# BT_Audio_iJoey.net
KiCad netlist of a schematic drawn in EAGLE
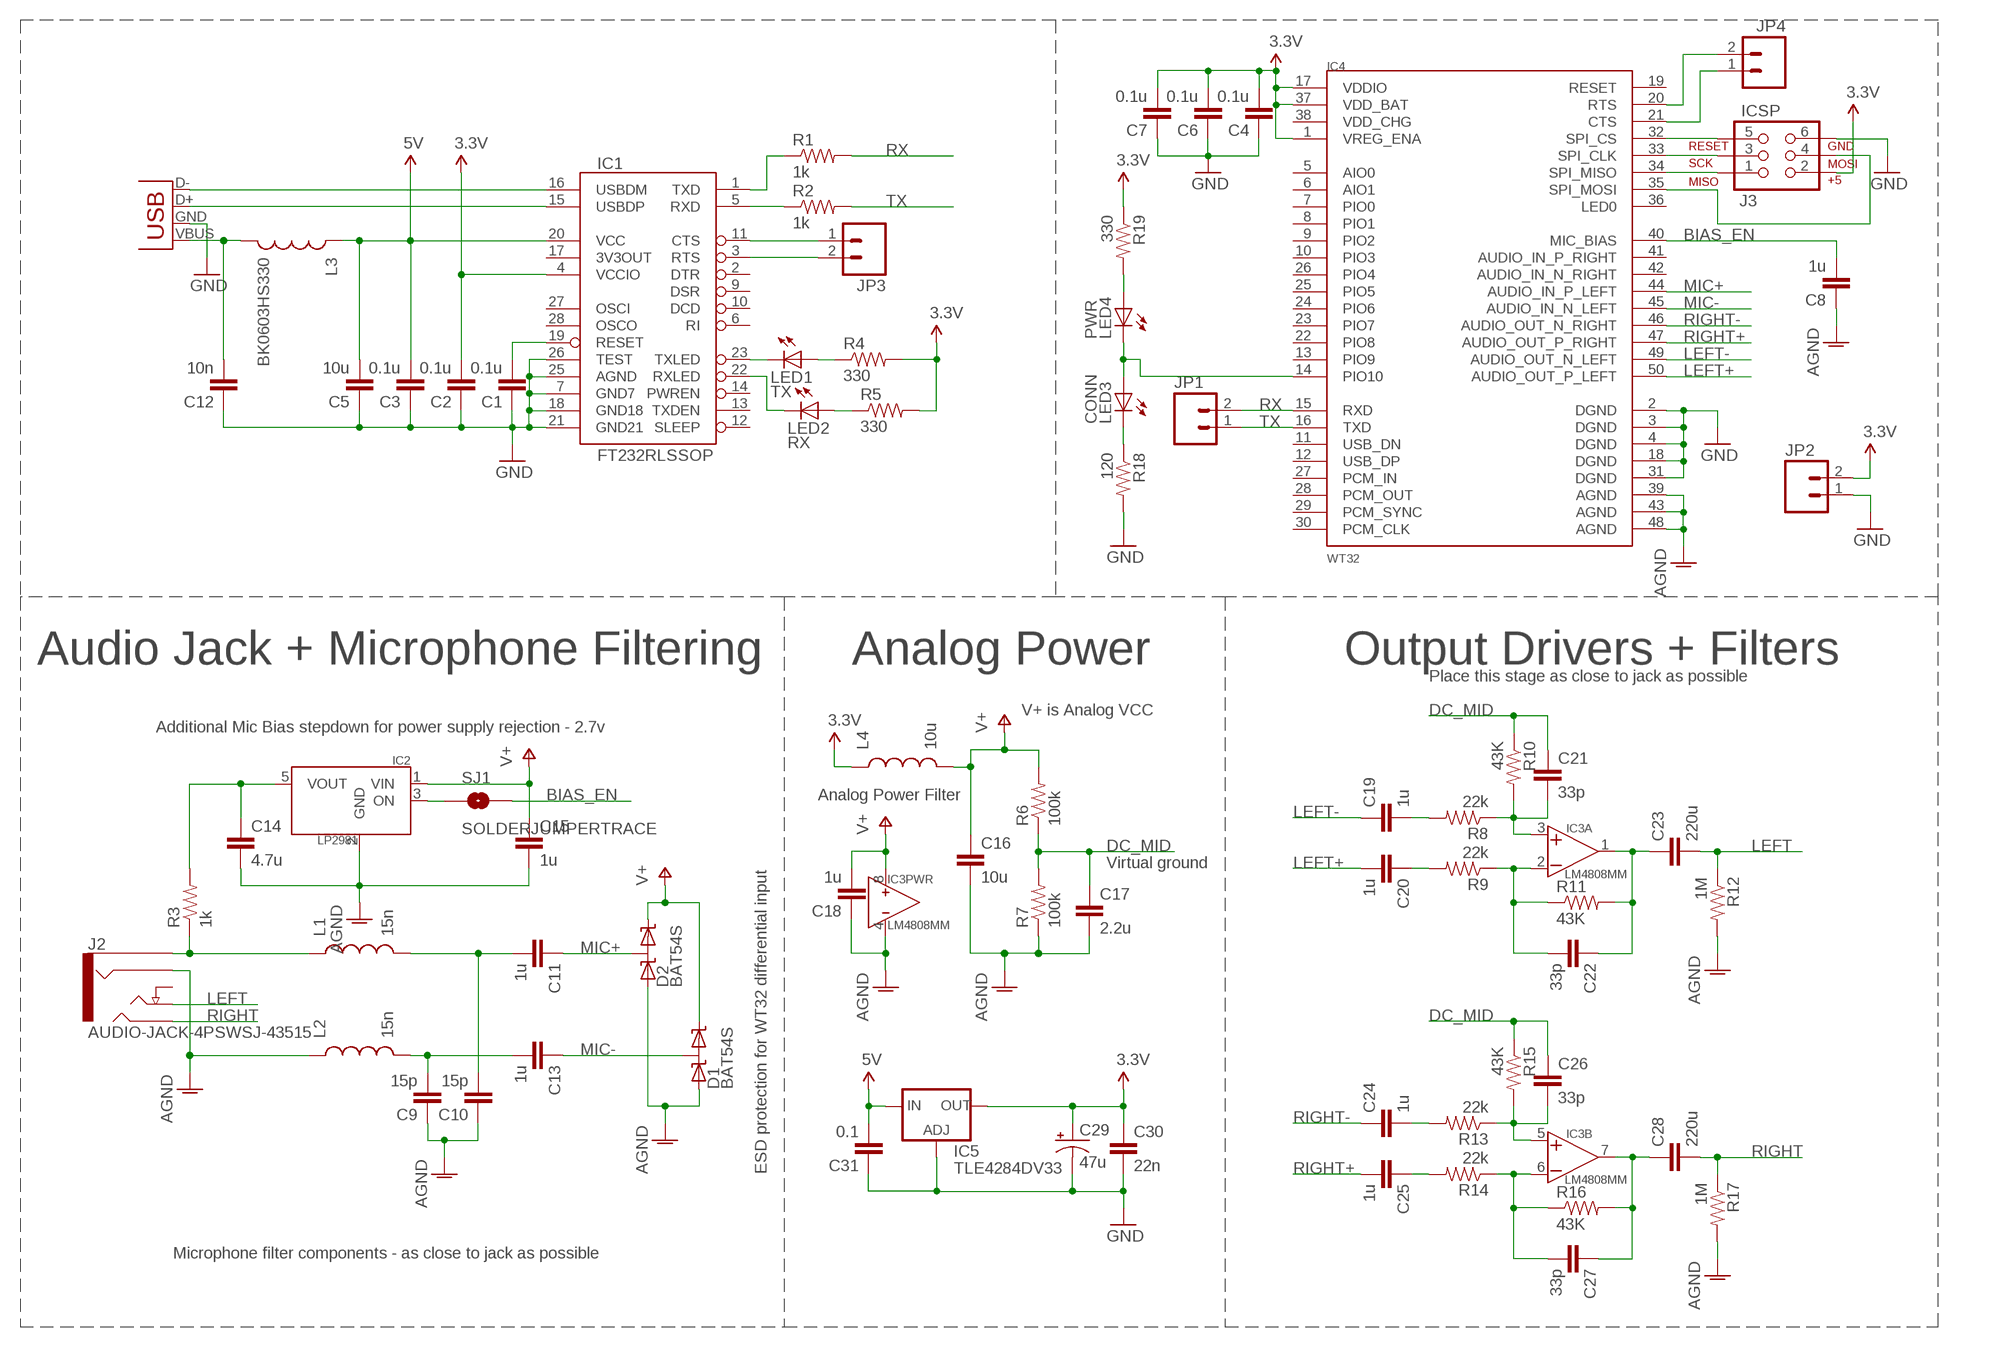
[diagram p0: schematic, sheet 1]

(export (version "E")
  (design (tool "Eeschema 10.0.6"))
  (components
    (comp (ref "C1")
      (value "0.1u")
      (footprint "eagle-import:0603-CAP")
      (libsource (lib "eagle-import") (part "CAP0603-CAP"))
    )
    (comp (ref "C2")
      (value "0.1u")
      (footprint "eagle-import:0603-CAP")
      (libsource (lib "eagle-import") (part "CAP0603-CAP"))
    )
    (comp (ref "C3")
      (value "0.1u")
      (footprint "eagle-import:0603-CAP")
      (libsource (lib "eagle-import") (part "CAP0603-CAP"))
    )
    (comp (ref "C4")
      (value "0.1u")
      (footprint "eagle-import:0603-CAP")
      (libsource (lib "eagle-import") (part "CAP0603-CAP"))
    )
    (comp (ref "C5")
      (value "10u")
      (footprint "eagle-import:0805")
      (libsource (lib "eagle-import") (part "CAP0805"))
    )
    (comp (ref "C6")
      (value "0.1u")
      (footprint "eagle-import:0603-CAP")
      (libsource (lib "eagle-import") (part "CAP0603-CAP"))
    )
    (comp (ref "C7")
      (value "0.1u")
      (footprint "eagle-import:0603-CAP")
      (libsource (lib "eagle-import") (part "CAP0603-CAP"))
    )
    (comp (ref "C8")
      (value "1u")
      (footprint "eagle-import:0603-CAP")
      (libsource (lib "eagle-import") (part "CAP0603-CAP"))
    )
    (comp (ref "C9")
      (value "15p")
      (footprint "eagle-import:0603-CAP")
      (libsource (lib "eagle-import") (part "CAP0603-CAP"))
    )
    (comp (ref "C10")
      (value "15p")
      (footprint "eagle-import:0603-CAP")
      (libsource (lib "eagle-import") (part "CAP0603-CAP"))
    )
    (comp (ref "C11")
      (value "1u")
      (footprint "eagle-import:0603-CAP")
      (libsource (lib "eagle-import") (part "CAP0603-CAP"))
    )
    (comp (ref "C12")
      (value "10n")
      (footprint "eagle-import:0603-CAP")
      (libsource (lib "eagle-import") (part "CAP0603-CAP"))
    )
    (comp (ref "C13")
      (value "1u")
      (footprint "eagle-import:0603-CAP")
      (libsource (lib "eagle-import") (part "CAP0603-CAP"))
    )
    (comp (ref "C14")
      (value "4.7u")
      (footprint "eagle-import:0603-CAP")
      (libsource (lib "eagle-import") (part "CAP0603-CAP"))
    )
    (comp (ref "C15")
      (value "1u")
      (footprint "eagle-import:0603-CAP")
      (libsource (lib "eagle-import") (part "CAP0603-CAP"))
    )
    (comp (ref "C16")
      (value "10u")
      (footprint "eagle-import:0603-CAP")
      (libsource (lib "eagle-import") (part "CAP0603-CAP"))
    )
    (comp (ref "C17")
      (value "2.2u")
      (footprint "eagle-import:0603-CAP")
      (libsource (lib "eagle-import") (part "CAP0603-CAP"))
    )
    (comp (ref "C18")
      (value "1u")
      (footprint "eagle-import:0603-CAP")
      (libsource (lib "eagle-import") (part "CAP0603-CAP"))
    )
    (comp (ref "C19")
      (value "1u")
      (footprint "eagle-import:0603-CAP")
      (libsource (lib "eagle-import") (part "CAP0603-CAP"))
    )
    (comp (ref "C20")
      (value "1u")
      (footprint "eagle-import:0603-CAP")
      (libsource (lib "eagle-import") (part "CAP0603-CAP"))
    )
    (comp (ref "C21")
      (value "33p")
      (footprint "eagle-import:0603-CAP")
      (libsource (lib "eagle-import") (part "CAP0603-CAP"))
    )
    (comp (ref "C22")
      (value "33p")
      (footprint "eagle-import:0603-CAP")
      (libsource (lib "eagle-import") (part "CAP0603-CAP"))
    )
    (comp (ref "C23")
      (value "220u")
      (footprint "eagle-import:1210")
      (libsource (lib "eagle-import") (part "CAP1210"))
    )
    (comp (ref "C24")
      (value "1u")
      (footprint "eagle-import:0603-CAP")
      (libsource (lib "eagle-import") (part "CAP0603-CAP"))
    )
    (comp (ref "C25")
      (value "1u")
      (footprint "eagle-import:0603-CAP")
      (libsource (lib "eagle-import") (part "CAP0603-CAP"))
    )
    (comp (ref "C26")
      (value "33p")
      (footprint "eagle-import:0603-CAP")
      (libsource (lib "eagle-import") (part "CAP0603-CAP"))
    )
    (comp (ref "C27")
      (value "33p")
      (footprint "eagle-import:0603-CAP")
      (libsource (lib "eagle-import") (part "CAP0603-CAP"))
    )
    (comp (ref "C28")
      (value "220u")
      (footprint "eagle-import:1210")
      (libsource (lib "eagle-import") (part "CAP1210"))
    )
    (comp (ref "C29")
      (value "47u")
      (footprint "eagle-import:PANASONIC_D")
      (libsource (lib "eagle-import") (part "CAP_POLD"))
    )
    (comp (ref "C30")
      (value "22n")
      (footprint "eagle-import:0603-CAP")
      (libsource (lib "eagle-import") (part "CAP0603-CAP"))
    )
    (comp (ref "C31")
      (value "0.1")
      (footprint "eagle-import:0603-CAP")
      (libsource (lib "eagle-import") (part "CAP0603-CAP"))
    )
    (comp (ref "D1")
      (value "BAT54S")
      (footprint "eagle-import:SOT23")
      (libsource (lib "eagle-import") (part "DIODE_DUAL_CLAMP"))
    )
    (comp (ref "D2")
      (value "BAT54S")
      (footprint "eagle-import:SOT23")
      (libsource (lib "eagle-import") (part "DIODE_DUAL_CLAMP"))
    )
    (comp (ref "IC1")
      (value "FT232RLSSOP")
      (footprint "eagle-import:SSOP28DB")
      (libsource (lib "eagle-import") (part "FT232RLSSOP"))
    )
    (comp (ref "IC2")
      (value "LP2981")
      (footprint "eagle-import:SOT23-5")
      (libsource (lib "eagle-import") (part "LP2981"))
    )
    (comp (ref "IC3")
      (value "LM4808MM")
      (footprint "eagle-import:SO8")
      (libsource (lib "eagle-import") (part "LM4808MM"))
    )
    (comp (ref "IC4")
      (value "WT32")
      (footprint "eagle-import:WT32")
      (libsource (lib "eagle-import") (part "WT32"))
    )
    (comp (ref "IC5")
      (value "TLE4284DV33")
      (footprint "eagle-import:V-REG_DPACK")
      (libsource (lib "eagle-import") (part "V_REG_317DPACK"))
    )
    (comp (ref "J1")
      (value "USB-A-H")
      (footprint "eagle-import:USB-A-H")
      (libsource (lib "eagle-import") (part "USB-A-H"))
    )
    (comp (ref "J2")
      (value "AUDIO-JACK-4PSWSJ-43515")
      (footprint "eagle-import:SJ-4351X")
      (libsource (lib "eagle-import") (part "AUDIO-JACK-4PSWSJ-43515"))
    )
    (comp (ref "J3")
      (value "ICSP")
      (footprint "eagle-import:2X3")
      (libsource (lib "eagle-import") (part "AVR_SPI_PRG_6PTH"))
    )
    (comp (ref "JP1")
      (value "M02PTH")
      (footprint "eagle-import:1X02")
      (libsource (lib "eagle-import") (part "M02PTH"))
    )
    (comp (ref "JP2")
      (value "M02PTH")
      (footprint "eagle-import:1X02")
      (libsource (lib "eagle-import") (part "M02PTH"))
    )
    (comp (ref "JP3")
      (value "M02PTH")
      (footprint "eagle-import:1X02")
      (libsource (lib "eagle-import") (part "M02PTH"))
    )
    (comp (ref "JP4")
      (value "M02PTH")
      (footprint "eagle-import:1X02")
      (libsource (lib "eagle-import") (part "M02PTH"))
    )
    (comp (ref "L1")
      (value "15n")
      (footprint "eagle-import:0603")
      (libsource (lib "eagle-import") (part "INDUCTOR0603"))
    )
    (comp (ref "L2")
      (value "15n")
      (footprint "eagle-import:0603")
      (libsource (lib "eagle-import") (part "INDUCTOR0603"))
    )
    (comp (ref "L3")
      (value "BK0603HS330")
      (footprint "eagle-import:0603")
      (libsource (lib "eagle-import") (part "INDUCTOR0603"))
    )
    (comp (ref "L4")
      (value "10u")
      (footprint "eagle-import:0603")
      (libsource (lib "eagle-import") (part "INDUCTOR0603"))
    )
    (comp (ref "LED1")
      (value "TX")
      (footprint "eagle-import:LED-0603")
      (libsource (lib "eagle-import") (part "LED0603"))
    )
    (comp (ref "LED2")
      (value "RX")
      (footprint "eagle-import:LED-0603")
      (libsource (lib "eagle-import") (part "LED0603"))
    )
    (comp (ref "LED3")
      (value "CONN")
      (footprint "eagle-import:LED-0603")
      (libsource (lib "eagle-import") (part "LED0603"))
    )
    (comp (ref "LED4")
      (value "PWR")
      (footprint "eagle-import:LED-0603")
      (libsource (lib "eagle-import") (part "LED0603"))
    )
    (comp (ref "R1")
      (value "1k")
      (footprint "eagle-import:0603-RES")
      (libsource (lib "eagle-import") (part "RESISTOR0603-RES"))
    )
    (comp (ref "R2")
      (value "1k")
      (footprint "eagle-import:0603-RES")
      (libsource (lib "eagle-import") (part "RESISTOR0603-RES"))
    )
    (comp (ref "R3")
      (value "1k")
      (footprint "eagle-import:0603-RES")
      (libsource (lib "eagle-import") (part "RESISTOR0603-RES"))
    )
    (comp (ref "R4")
      (value "330")
      (footprint "eagle-import:0603-RES")
      (libsource (lib "eagle-import") (part "RESISTOR0603-RES"))
    )
    (comp (ref "R5")
      (value "330")
      (footprint "eagle-import:0603-RES")
      (libsource (lib "eagle-import") (part "RESISTOR0603-RES"))
    )
    (comp (ref "R6")
      (value "100k")
      (footprint "eagle-import:0603-RES")
      (libsource (lib "eagle-import") (part "RESISTOR0603-RES"))
    )
    (comp (ref "R7")
      (value "100k")
      (footprint "eagle-import:0603-RES")
      (libsource (lib "eagle-import") (part "RESISTOR0603-RES"))
    )
    (comp (ref "R8")
      (value "22k")
      (footprint "eagle-import:0603-RES")
      (libsource (lib "eagle-import") (part "RESISTOR0603-RES"))
    )
    (comp (ref "R9")
      (value "22k")
      (footprint "eagle-import:0603-RES")
      (libsource (lib "eagle-import") (part "RESISTOR0603-RES"))
    )
    (comp (ref "R10")
      (value "43K")
      (footprint "eagle-import:0603-RES")
      (libsource (lib "eagle-import") (part "RESISTOR0603-RES"))
    )
    (comp (ref "R11")
      (value "43K")
      (footprint "eagle-import:0603-RES")
      (libsource (lib "eagle-import") (part "RESISTOR0603-RES"))
    )
    (comp (ref "R12")
      (value "1M")
      (footprint "eagle-import:0603-RES")
      (libsource (lib "eagle-import") (part "RESISTOR0603-RES"))
    )
    (comp (ref "R13")
      (value "22k")
      (footprint "eagle-import:0603-RES")
      (libsource (lib "eagle-import") (part "RESISTOR0603-RES"))
    )
    (comp (ref "R14")
      (value "22k")
      (footprint "eagle-import:0603-RES")
      (libsource (lib "eagle-import") (part "RESISTOR0603-RES"))
    )
    (comp (ref "R15")
      (value "43K")
      (footprint "eagle-import:0603-RES")
      (libsource (lib "eagle-import") (part "RESISTOR0603-RES"))
    )
    (comp (ref "R16")
      (value "43K")
      (footprint "eagle-import:0603-RES")
      (libsource (lib "eagle-import") (part "RESISTOR0603-RES"))
    )
    (comp (ref "R17")
      (value "1M")
      (footprint "eagle-import:0603-RES")
      (libsource (lib "eagle-import") (part "RESISTOR0603-RES"))
    )
    (comp (ref "R18")
      (value "120")
      (footprint "eagle-import:0603-RES")
      (libsource (lib "eagle-import") (part "RESISTOR0603-RES"))
    )
    (comp (ref "R19")
      (value "330")
      (footprint "eagle-import:0603-RES")
      (libsource (lib "eagle-import") (part "RESISTOR0603-RES"))
    )
    (comp (ref "SJ1")
      (value "SOLDERJUMPERTRACE")
      (footprint "eagle-import:SJ_2S-TRACE")
      (libsource (lib "eagle-import") (part "SOLDERJUMPERTRACE"))
    )
  )
  (nets
    (net (code "1") (name "/BIAS_EN") (class "Default")
      (node (ref "C8") (pin "2") (pinfunction "2_2") (pintype "passive"))
      (node (ref "IC4") (pin "40") (pinfunction "MIC_BIAS_40") (pintype "bidirectional"))
      (node (ref "SJ1") (pin "2") (pinfunction "2_2") (pintype "passive"))
    )
    (net (code "2") (name "/DC_MID") (class "Default")
      (node (ref "C17") (pin "1") (pinfunction "1_1") (pintype "passive"))
      (node (ref "C21") (pin "1") (pinfunction "1_1") (pintype "passive"))
      (node (ref "C26") (pin "1") (pinfunction "1_1") (pintype "passive"))
      (node (ref "R10") (pin "1") (pinfunction "1_1") (pintype "passive"))
      (node (ref "R15") (pin "1") (pinfunction "1_1") (pintype "passive"))
      (node (ref "R6") (pin "1") (pinfunction "1_1") (pintype "passive"))
      (node (ref "R7") (pin "2") (pinfunction "2_2") (pintype "passive"))
    )
    (net (code "3") (name "/LEFT") (class "Default")
      (node (ref "C23") (pin "2") (pinfunction "2_2") (pintype "passive"))
      (node (ref "J2") (pin "2") (pinfunction "TIP_2") (pintype "bidirectional"))
      (node (ref "R12") (pin "1") (pinfunction "1_1") (pintype "passive"))
    )
    (net (code "4") (name "/LEFT+") (class "Default")
      (node (ref "C20") (pin "2") (pinfunction "2_2") (pintype "passive"))
      (node (ref "IC4") (pin "50") (pinfunction "AUDIO_OUT_P_LEFT_50") (pintype "bidirectional"))
    )
    (net (code "5") (name "/LEFT-") (class "Default")
      (node (ref "C19") (pin "1") (pinfunction "1_1") (pintype "passive"))
      (node (ref "IC4") (pin "49") (pinfunction "AUDIO_OUT_N_LEFT_49") (pintype "bidirectional"))
    )
    (net (code "6") (name "/MIC+") (class "Default")
      (node (ref "C11") (pin "1") (pinfunction "1_1") (pintype "passive"))
      (node (ref "D2") (pin "3") (pinfunction "COM_3") (pintype "passive"))
      (node (ref "IC4") (pin "44") (pinfunction "AUDIO_IN_P_LEFT_44") (pintype "bidirectional"))
    )
    (net (code "7") (name "/MIC-") (class "Default")
      (node (ref "C13") (pin "1") (pinfunction "1_1") (pintype "passive"))
      (node (ref "D1") (pin "3") (pinfunction "COM_3") (pintype "passive"))
      (node (ref "IC4") (pin "45") (pinfunction "AUDIO_IN_N_LEFT_45") (pintype "bidirectional"))
    )
    (net (code "8") (name "/RIGHT") (class "Default")
      (node (ref "C28") (pin "2") (pinfunction "2_2") (pintype "passive"))
      (node (ref "J2") (pin "3") (pinfunction "RING1_3") (pintype "bidirectional"))
      (node (ref "R17") (pin "1") (pinfunction "1_1") (pintype "passive"))
    )
    (net (code "9") (name "/RIGHT+") (class "Default")
      (node (ref "C25") (pin "2") (pinfunction "2_2") (pintype "passive"))
      (node (ref "IC4") (pin "47") (pinfunction "AUDIO_OUT_P_RIGHT_47") (pintype "bidirectional"))
    )
    (net (code "10") (name "/RIGHT-") (class "Default")
      (node (ref "C24") (pin "1") (pinfunction "1_1") (pintype "passive"))
      (node (ref "IC4") (pin "46") (pinfunction "AUDIO_OUT_N_RIGHT_46") (pintype "bidirectional"))
    )
    (net (code "11") (name "/RX") (class "Default")
      (node (ref "IC4") (pin "15") (pinfunction "RXD_15") (pintype "bidirectional"))
      (node (ref "JP1") (pin "2") (pinfunction "2_2") (pintype "passive"))
      (node (ref "R1") (pin "2") (pinfunction "2_2") (pintype "passive"))
    )
    (net (code "12") (name "/TX") (class "Default")
      (node (ref "IC4") (pin "16") (pinfunction "TXD_16") (pintype "bidirectional"))
      (node (ref "JP1") (pin "1") (pinfunction "1_1") (pintype "passive"))
      (node (ref "R2") (pin "2") (pinfunction "2_2") (pintype "passive"))
    )
    (net (code "13") (name "3.3V") (class "Default")
      (node (ref "C2") (pin "2") (pinfunction "2_2") (pintype "passive"))
      (node (ref "C29") (pin "+") (pinfunction "+_+") (pintype "passive"))
      (node (ref "C30") (pin "1") (pinfunction "1_1") (pintype "passive"))
      (node (ref "C4") (pin "2") (pinfunction "2_2") (pintype "passive"))
      (node (ref "C6") (pin "2") (pinfunction "2_2") (pintype "passive"))
      (node (ref "C7") (pin "2") (pinfunction "2_2") (pintype "passive"))
      (node (ref "IC1") (pin "4") (pinfunction "VCCIO_4") (pintype "power_in"))
      (node (ref "IC4") (pin "1") (pinfunction "VREG_ENA_1") (pintype "bidirectional"))
      (node (ref "IC4") (pin "17") (pinfunction "VDDIO_17") (pintype "bidirectional"))
      (node (ref "IC4") (pin "37") (pinfunction "VDD_BAT_37") (pintype "bidirectional"))
      (node (ref "IC5") (pin "4") (pinfunction "OUT_4") (pintype "output"))
      (node (ref "J3") (pin "2") (pinfunction "2_2") (pintype "passive"))
      (node (ref "JP2") (pin "2") (pinfunction "2_2") (pintype "passive"))
      (node (ref "L4") (pin "1") (pinfunction "1_1") (pintype "passive"))
      (node (ref "R19") (pin "1") (pinfunction "1_1") (pintype "passive"))
      (node (ref "R4") (pin "2") (pinfunction "2_2") (pintype "passive"))
      (node (ref "R5") (pin "2") (pinfunction "2_2") (pintype "passive"))
    )
    (net (code "14") (name "5V") (class "Default")
      (node (ref "C3") (pin "2") (pinfunction "2_2") (pintype "passive"))
      (node (ref "C31") (pin "2") (pinfunction "2_2") (pintype "passive"))
      (node (ref "C5") (pin "2") (pinfunction "2_2") (pintype "passive"))
      (node (ref "IC1") (pin "20") (pinfunction "VCC_20") (pintype "power_in"))
      (node (ref "IC5") (pin "3") (pinfunction "IN_3") (pintype "input"))
      (node (ref "L3") (pin "1") (pinfunction "1_1") (pintype "passive"))
    )
    (net (code "15") (name "AGND") (class "Default")
      (node (ref "C10") (pin "1") (pinfunction "1_1") (pintype "passive"))
      (node (ref "C14") (pin "2") (pinfunction "2_2") (pintype "passive"))
      (node (ref "C15") (pin "2") (pinfunction "2_2") (pintype "passive"))
      (node (ref "C16") (pin "2") (pinfunction "2_2") (pintype "passive"))
      (node (ref "C17") (pin "2") (pinfunction "2_2") (pintype "passive"))
      (node (ref "C18") (pin "1") (pinfunction "1_1") (pintype "passive"))
      (node (ref "C8") (pin "1") (pinfunction "1_1") (pintype "passive"))
      (node (ref "C9") (pin "1") (pinfunction "1_1") (pintype "passive"))
      (node (ref "D1") (pin "1") (pinfunction "AN_1") (pintype "passive"))
      (node (ref "D2") (pin "1") (pinfunction "AN_1") (pintype "passive"))
      (node (ref "IC2") (pin "2") (pinfunction "GND_2") (pintype "bidirectional"))
      (node (ref "IC3") (pin "4") (pinfunction "-V_4") (pintype "bidirectional"))
      (node (ref "IC4") (pin "39") (pinfunction "AGND_39") (pintype "bidirectional"))
      (node (ref "IC4") (pin "43") (pinfunction "AGND_43") (pintype "bidirectional"))
      (node (ref "IC4") (pin "48") (pinfunction "AGND_48") (pintype "bidirectional"))
      (node (ref "J2") (pin "4") (pinfunction "RING2_4") (pintype "bidirectional"))
      (node (ref "L2") (pin "1") (pinfunction "1_1") (pintype "passive"))
      (node (ref "R12") (pin "2") (pinfunction "2_2") (pintype "passive"))
      (node (ref "R17") (pin "2") (pinfunction "2_2") (pintype "passive"))
      (node (ref "R7") (pin "1") (pinfunction "1_1") (pintype "passive"))
    )
    (net (code "16") (name "GND") (class "Default")
      (node (ref "C1") (pin "1") (pinfunction "1_1") (pintype "passive"))
      (node (ref "C12") (pin "1") (pinfunction "1_1") (pintype "passive"))
      (node (ref "C2") (pin "1") (pinfunction "1_1") (pintype "passive"))
      (node (ref "C29") (pin "-") (pinfunction "-_-") (pintype "passive"))
      (node (ref "C3") (pin "1") (pinfunction "1_1") (pintype "passive"))
      (node (ref "C30") (pin "2") (pinfunction "2_2") (pintype "passive"))
      (node (ref "C31") (pin "1") (pinfunction "1_1") (pintype "passive"))
      (node (ref "C4") (pin "1") (pinfunction "1_1") (pintype "passive"))
      (node (ref "C5") (pin "1") (pinfunction "1_1") (pintype "passive"))
      (node (ref "C6") (pin "1") (pinfunction "1_1") (pintype "passive"))
      (node (ref "C7") (pin "1") (pinfunction "1_1") (pintype "passive"))
      (node (ref "IC1") (pin "18") (pinfunction "GND18_18") (pintype "power_in"))
      (node (ref "IC1") (pin "21") (pinfunction "GND21_21") (pintype "power_in"))
      (node (ref "IC1") (pin "25") (pinfunction "AGND_25") (pintype "power_in"))
      (node (ref "IC1") (pin "26") (pinfunction "TEST_26") (pintype "input"))
      (node (ref "IC1") (pin "7") (pinfunction "GND7_7") (pintype "power_in"))
      (node (ref "IC4") (pin "18") (pinfunction "DGND_18") (pintype "bidirectional"))
      (node (ref "IC4") (pin "2") (pinfunction "DGND_2") (pintype "bidirectional"))
      (node (ref "IC4") (pin "3") (pinfunction "DGND_3") (pintype "bidirectional"))
      (node (ref "IC4") (pin "31") (pinfunction "DGND_31") (pintype "bidirectional"))
      (node (ref "IC4") (pin "4") (pinfunction "DGND_4") (pintype "bidirectional"))
      (node (ref "IC5") (pin "1") (pinfunction "ADJ_1") (pintype "input"))
      (node (ref "J1") (pin "GND") (pinfunction "VBUS_GND") (pintype "bidirectional"))
      (node (ref "J3") (pin "6") (pinfunction "6_6") (pintype "passive"))
      (node (ref "JP2") (pin "1") (pinfunction "1_1") (pintype "passive"))
      (node (ref "R18") (pin "2") (pinfunction "2_2") (pintype "passive"))
    )
    (net (code "17") (name "Net-(C10-Pad2)") (class "Default")
      (node (ref "C10") (pin "2") (pinfunction "2_2") (pintype "passive"))
      (node (ref "C11") (pin "2") (pinfunction "2_2") (pintype "passive"))
      (node (ref "L1") (pin "2") (pinfunction "2_2") (pintype "passive"))
    )
    (net (code "18") (name "Net-(C13-Pad2)") (class "Default")
      (node (ref "C13") (pin "2") (pinfunction "2_2") (pintype "passive"))
      (node (ref "C9") (pin "2") (pinfunction "2_2") (pintype "passive"))
      (node (ref "L2") (pin "2") (pinfunction "2_2") (pintype "passive"))
    )
    (net (code "19") (name "Net-(C19-Pad2)") (class "Default")
      (node (ref "C19") (pin "2") (pinfunction "2_2") (pintype "passive"))
      (node (ref "R8") (pin "2") (pinfunction "2_2") (pintype "passive"))
    )
    (net (code "20") (name "Net-(C20-Pad1)") (class "Default")
      (node (ref "C20") (pin "1") (pinfunction "1_1") (pintype "passive"))
      (node (ref "R9") (pin "2") (pinfunction "2_2") (pintype "passive"))
    )
    (net (code "21") (name "Net-(C24-Pad2)") (class "Default")
      (node (ref "C24") (pin "2") (pinfunction "2_2") (pintype "passive"))
      (node (ref "R13") (pin "2") (pinfunction "2_2") (pintype "passive"))
    )
    (net (code "22") (name "Net-(C25-Pad1)") (class "Default")
      (node (ref "C25") (pin "1") (pinfunction "1_1") (pintype "passive"))
      (node (ref "R14") (pin "2") (pinfunction "2_2") (pintype "passive"))
    )
    (net (code "23") (name "Net-(IC1-CTS)") (class "Default")
      (node (ref "IC1") (pin "11") (pinfunction "CTS_11") (pintype "input"))
      (node (ref "JP3") (pin "1") (pinfunction "1_1") (pintype "passive"))
    )
    (net (code "24") (name "Net-(IC1-RESET)") (class "Default")
      (node (ref "C1") (pin "2") (pinfunction "2_2") (pintype "passive"))
      (node (ref "IC1") (pin "19") (pinfunction "RESET_19") (pintype "input"))
    )
    (net (code "25") (name "Net-(IC1-RTS)") (class "Default")
      (node (ref "IC1") (pin "3") (pinfunction "RTS_3") (pintype "output"))
      (node (ref "JP3") (pin "2") (pinfunction "2_2") (pintype "passive"))
    )
    (net (code "26") (name "Net-(IC1-RXD)") (class "Default")
      (node (ref "IC1") (pin "5") (pinfunction "RXD_5") (pintype "input"))
      (node (ref "R2") (pin "1") (pinfunction "1_1") (pintype "passive"))
    )
    (net (code "27") (name "Net-(IC1-RXLED)") (class "Default")
      (node (ref "IC1") (pin "22") (pinfunction "RXLED_22") (pintype "input"))
      (node (ref "LED2") (pin "C") (pinfunction "C_C") (pintype "passive"))
    )
    (net (code "28") (name "Net-(IC1-TXD)") (class "Default")
      (node (ref "IC1") (pin "1") (pinfunction "TXD_1") (pintype "output"))
      (node (ref "R1") (pin "1") (pinfunction "1_1") (pintype "passive"))
    )
    (net (code "29") (name "Net-(IC1-TXLED)") (class "Default")
      (node (ref "IC1") (pin "23") (pinfunction "TXLED_23") (pintype "input"))
      (node (ref "LED1") (pin "C") (pinfunction "C_C") (pintype "passive"))
    )
    (net (code "30") (name "Net-(IC1-USBDM)") (class "Default")
      (node (ref "IC1") (pin "16") (pinfunction "USBDM_16") (pintype "bidirectional"))
      (node (ref "J1") (pin "D-") (pinfunction "D+_D-") (pintype "bidirectional"))
    )
    (net (code "31") (name "Net-(IC1-USBDP)") (class "Default")
      (node (ref "IC1") (pin "15") (pinfunction "USBDP_15") (pintype "bidirectional"))
      (node (ref "J1") (pin "D+") (pinfunction "D-_D+") (pintype "bidirectional"))
    )
    (net (code "32") (name "Net-(IC2-ON)") (class "Default")
      (node (ref "IC2") (pin "3") (pinfunction "ON_3") (pintype "bidirectional"))
      (node (ref "SJ1") (pin "1") (pinfunction "1_1") (pintype "passive"))
    )
    (net (code "33") (name "Net-(IC2-VOUT)") (class "Default")
      (node (ref "C14") (pin "1") (pinfunction "1_1") (pintype "passive"))
      (node (ref "IC2") (pin "5") (pinfunction "VOUT_5") (pintype "bidirectional"))
      (node (ref "R3") (pin "2") (pinfunction "2_2") (pintype "passive"))
    )
    (net (code "34") (name "Net-(IC3A-+)") (class "Default")
      (node (ref "C21") (pin "2") (pinfunction "2_2") (pintype "passive"))
      (node (ref "IC3") (pin "3") (pinfunction "+_3") (pintype "bidirectional"))
      (node (ref "R10") (pin "2") (pinfunction "2_2") (pintype "passive"))
      (node (ref "R8") (pin "1") (pinfunction "1_1") (pintype "passive"))
    )
    (net (code "35") (name "Net-(IC3A--)") (class "Default")
      (node (ref "C22") (pin "2") (pinfunction "2_2") (pintype "passive"))
      (node (ref "IC3") (pin "2") (pinfunction "-_2") (pintype "bidirectional"))
      (node (ref "R11") (pin "1") (pinfunction "1_1") (pintype "passive"))
      (node (ref "R9") (pin "1") (pinfunction "1_1") (pintype "passive"))
    )
    (net (code "36") (name "Net-(IC3A-O)") (class "Default")
      (node (ref "C22") (pin "1") (pinfunction "1_1") (pintype "passive"))
      (node (ref "C23") (pin "1") (pinfunction "1_1") (pintype "passive"))
      (node (ref "IC3") (pin "1") (pinfunction "O_1") (pintype "bidirectional"))
      (node (ref "R11") (pin "2") (pinfunction "2_2") (pintype "passive"))
    )
    (net (code "37") (name "Net-(IC3B-+)") (class "Default")
      (node (ref "C26") (pin "2") (pinfunction "2_2") (pintype "passive"))
      (node (ref "IC3") (pin "5") (pinfunction "+_5") (pintype "bidirectional"))
      (node (ref "R13") (pin "1") (pinfunction "1_1") (pintype "passive"))
      (node (ref "R15") (pin "2") (pinfunction "2_2") (pintype "passive"))
    )
    (net (code "38") (name "Net-(IC3B--)") (class "Default")
      (node (ref "C27") (pin "2") (pinfunction "2_2") (pintype "passive"))
      (node (ref "IC3") (pin "6") (pinfunction "-_6") (pintype "bidirectional"))
      (node (ref "R14") (pin "1") (pinfunction "1_1") (pintype "passive"))
      (node (ref "R16") (pin "1") (pinfunction "1_1") (pintype "passive"))
    )
    (net (code "39") (name "Net-(IC3B-O)") (class "Default")
      (node (ref "C27") (pin "1") (pinfunction "1_1") (pintype "passive"))
      (node (ref "C28") (pin "1") (pinfunction "1_1") (pintype "passive"))
      (node (ref "IC3") (pin "7") (pinfunction "O_7") (pintype "bidirectional"))
      (node (ref "R16") (pin "2") (pinfunction "2_2") (pintype "passive"))
    )
    (net (code "40") (name "Net-(IC4-CTS)") (class "Default")
      (node (ref "IC4") (pin "21") (pinfunction "CTS_21") (pintype "bidirectional"))
      (node (ref "JP4") (pin "1") (pinfunction "1_1") (pintype "passive"))
    )
    (net (code "41") (name "Net-(IC4-PIO10)") (class "Default")
      (node (ref "IC4") (pin "14") (pinfunction "PIO10_14") (pintype "bidirectional"))
      (node (ref "LED3") (pin "A") (pinfunction "A_A") (pintype "passive"))
      (node (ref "LED4") (pin "C") (pinfunction "C_C") (pintype "passive"))
    )
    (net (code "42") (name "Net-(IC4-RTS)") (class "Default")
      (node (ref "IC4") (pin "20") (pinfunction "RTS_20") (pintype "bidirectional"))
      (node (ref "JP4") (pin "2") (pinfunction "2_2") (pintype "passive"))
    )
    (net (code "43") (name "Net-(IC4-SPI_CLK)") (class "Default")
      (node (ref "IC4") (pin "33") (pinfunction "SPI_CLK_33") (pintype "bidirectional"))
      (node (ref "J3") (pin "3") (pinfunction "3_3") (pintype "passive"))
    )
    (net (code "44") (name "Net-(IC4-SPI_CS)") (class "Default")
      (node (ref "IC4") (pin "32") (pinfunction "SPI_CS_32") (pintype "bidirectional"))
      (node (ref "J3") (pin "5") (pinfunction "5_5") (pintype "passive"))
    )
    (net (code "45") (name "Net-(IC4-SPI_MISO)") (class "Default")
      (node (ref "IC4") (pin "34") (pinfunction "SPI_MISO_34") (pintype "bidirectional"))
      (node (ref "J3") (pin "1") (pinfunction "1_1") (pintype "passive"))
    )
    (net (code "46") (name "Net-(IC4-SPI_MOSI)") (class "Default")
      (node (ref "IC4") (pin "35") (pinfunction "SPI_MOSI_35") (pintype "bidirectional"))
      (node (ref "J3") (pin "4") (pinfunction "4_4") (pintype "passive"))
    )
    (net (code "47") (name "Net-(J1-GND)") (class "Default")
      (node (ref "C12") (pin "2") (pinfunction "2_2") (pintype "passive"))
      (node (ref "J1") (pin "VBUS") (pinfunction "GND_VBUS") (pintype "bidirectional"))
      (node (ref "L3") (pin "2") (pinfunction "2_2") (pintype "passive"))
    )
    (net (code "48") (name "Net-(J2-SLEEVE)") (class "Default")
      (node (ref "J2") (pin "1") (pinfunction "SLEEVE_1") (pintype "bidirectional"))
      (node (ref "L1") (pin "1") (pinfunction "1_1") (pintype "passive"))
      (node (ref "R3") (pin "1") (pinfunction "1_1") (pintype "passive"))
    )
    (net (code "49") (name "Net-(LED1-PadA)") (class "Default")
      (node (ref "LED1") (pin "A") (pinfunction "A_A") (pintype "passive"))
      (node (ref "R4") (pin "1") (pinfunction "1_1") (pintype "passive"))
    )
    (net (code "50") (name "Net-(LED2-PadA)") (class "Default")
      (node (ref "LED2") (pin "A") (pinfunction "A_A") (pintype "passive"))
      (node (ref "R5") (pin "1") (pinfunction "1_1") (pintype "passive"))
    )
    (net (code "51") (name "Net-(LED3-PadC)") (class "Default")
      (node (ref "LED3") (pin "C") (pinfunction "C_C") (pintype "passive"))
      (node (ref "R18") (pin "1") (pinfunction "1_1") (pintype "passive"))
    )
    (net (code "52") (name "Net-(LED4-PadA)") (class "Default")
      (node (ref "LED4") (pin "A") (pinfunction "A_A") (pintype "passive"))
      (node (ref "R19") (pin "2") (pinfunction "2_2") (pintype "passive"))
    )
    (net (code "53") (name "V+") (class "Default")
      (node (ref "C15") (pin "1") (pinfunction "1_1") (pintype "passive"))
      (node (ref "C16") (pin "1") (pinfunction "1_1") (pintype "passive"))
      (node (ref "C18") (pin "2") (pinfunction "2_2") (pintype "passive"))
      (node (ref "D1") (pin "2") (pinfunction "CAT_2") (pintype "passive"))
      (node (ref "D2") (pin "2") (pinfunction "CAT_2") (pintype "passive"))
      (node (ref "IC2") (pin "1") (pinfunction "VIN_1") (pintype "bidirectional"))
      (node (ref "IC3") (pin "8") (pinfunction "+V_8") (pintype "bidirectional"))
      (node (ref "L4") (pin "2") (pinfunction "2_2") (pintype "passive"))
      (node (ref "R6") (pin "2") (pinfunction "2_2") (pintype "passive"))
    )
    (net (code "54") (name "unconnected-(IC1-3V3OUT-Pad17)") (class "Default")
      (node (ref "IC1") (pin "17") (pinfunction "3V3OUT_17") (pintype "output"))
    )
    (net (code "55") (name "unconnected-(IC1-DCD-Pad10)") (class "Default")
      (node (ref "IC1") (pin "10") (pinfunction "DCD_10") (pintype "input"))
    )
    (net (code "56") (name "unconnected-(IC1-DSR-Pad9)") (class "Default")
      (node (ref "IC1") (pin "9") (pinfunction "DSR_9") (pintype "input"))
    )
    (net (code "57") (name "unconnected-(IC1-DTR-Pad2)") (class "Default")
      (node (ref "IC1") (pin "2") (pinfunction "DTR_2") (pintype "output"))
    )
    (net (code "58") (name "unconnected-(IC1-OSCI-Pad27)") (class "Default")
      (node (ref "IC1") (pin "27") (pinfunction "OSCI_27") (pintype "input"))
    )
    (net (code "59") (name "unconnected-(IC1-OSCO-Pad28)") (class "Default")
      (node (ref "IC1") (pin "28") (pinfunction "OSCO_28") (pintype "output"))
    )
    (net (code "60") (name "unconnected-(IC1-PWREN-Pad14)") (class "Default")
      (node (ref "IC1") (pin "14") (pinfunction "PWREN_14") (pintype "input"))
    )
    (net (code "61") (name "unconnected-(IC1-RI-Pad6)") (class "Default")
      (node (ref "IC1") (pin "6") (pinfunction "RI_6") (pintype "input"))
    )
    (net (code "62") (name "unconnected-(IC1-SLEEP-Pad12)") (class "Default")
      (node (ref "IC1") (pin "12") (pinfunction "SLEEP_12") (pintype "input"))
    )
    (net (code "63") (name "unconnected-(IC1-TXDEN-Pad13)") (class "Default")
      (node (ref "IC1") (pin "13") (pinfunction "TXDEN_13") (pintype "input"))
    )
    (net (code "64") (name "unconnected-(IC4-AIO0-Pad5)") (class "Default")
      (node (ref "IC4") (pin "5") (pinfunction "AIO0_5") (pintype "bidirectional"))
    )
    (net (code "65") (name "unconnected-(IC4-AIO1-Pad6)") (class "Default")
      (node (ref "IC4") (pin "6") (pinfunction "AIO1_6") (pintype "bidirectional"))
    )
    (net (code "66") (name "unconnected-(IC4-AUDIO_IN_N_RIGHT-Pad42)") (class "Default")
      (node (ref "IC4") (pin "42") (pinfunction "AUDIO_IN_N_RIGHT_42") (pintype "bidirectional"))
    )
    (net (code "67") (name "unconnected-(IC4-AUDIO_IN_P_RIGHT-Pad41)") (class "Default")
      (node (ref "IC4") (pin "41") (pinfunction "AUDIO_IN_P_RIGHT_41") (pintype "bidirectional"))
    )
    (net (code "68") (name "unconnected-(IC4-LED0-Pad36)") (class "Default")
      (node (ref "IC4") (pin "36") (pinfunction "LED0_36") (pintype "bidirectional"))
    )
    (net (code "69") (name "unconnected-(IC4-PCM_CLK-Pad30)") (class "Default")
      (node (ref "IC4") (pin "30") (pinfunction "PCM_CLK_30") (pintype "bidirectional"))
    )
    (net (code "70") (name "unconnected-(IC4-PCM_IN-Pad27)") (class "Default")
      (node (ref "IC4") (pin "27") (pinfunction "PCM_IN_27") (pintype "bidirectional"))
    )
    (net (code "71") (name "unconnected-(IC4-PCM_OUT-Pad28)") (class "Default")
      (node (ref "IC4") (pin "28") (pinfunction "PCM_OUT_28") (pintype "bidirectional"))
    )
    (net (code "72") (name "unconnected-(IC4-PCM_SYNC-Pad29)") (class "Default")
      (node (ref "IC4") (pin "29") (pinfunction "PCM_SYNC_29") (pintype "bidirectional"))
    )
    (net (code "73") (name "unconnected-(IC4-PIO0-Pad7)") (class "Default")
      (node (ref "IC4") (pin "7") (pinfunction "PIO0_7") (pintype "bidirectional"))
    )
    (net (code "74") (name "unconnected-(IC4-PIO1-Pad8)") (class "Default")
      (node (ref "IC4") (pin "8") (pinfunction "PIO1_8") (pintype "bidirectional"))
    )
    (net (code "75") (name "unconnected-(IC4-PIO2-Pad9)") (class "Default")
      (node (ref "IC4") (pin "9") (pinfunction "PIO2_9") (pintype "bidirectional"))
    )
    (net (code "76") (name "unconnected-(IC4-PIO3-Pad10)") (class "Default")
      (node (ref "IC4") (pin "10") (pinfunction "PIO3_10") (pintype "bidirectional"))
    )
    (net (code "77") (name "unconnected-(IC4-PIO4-Pad26)") (class "Default")
      (node (ref "IC4") (pin "26") (pinfunction "PIO4_26") (pintype "bidirectional"))
    )
    (net (code "78") (name "unconnected-(IC4-PIO5-Pad25)") (class "Default")
      (node (ref "IC4") (pin "25") (pinfunction "PIO5_25") (pintype "bidirectional"))
    )
    (net (code "79") (name "unconnected-(IC4-PIO6-Pad24)") (class "Default")
      (node (ref "IC4") (pin "24") (pinfunction "PIO6_24") (pintype "bidirectional"))
    )
    (net (code "80") (name "unconnected-(IC4-PIO7-Pad23)") (class "Default")
      (node (ref "IC4") (pin "23") (pinfunction "PIO7_23") (pintype "bidirectional"))
    )
    (net (code "81") (name "unconnected-(IC4-PIO8-Pad22)") (class "Default")
      (node (ref "IC4") (pin "22") (pinfunction "PIO8_22") (pintype "bidirectional"))
    )
    (net (code "82") (name "unconnected-(IC4-PIO9-Pad13)") (class "Default")
      (node (ref "IC4") (pin "13") (pinfunction "PIO9_13") (pintype "bidirectional"))
    )
    (net (code "83") (name "unconnected-(IC4-RESET-Pad19)") (class "Default")
      (node (ref "IC4") (pin "19") (pinfunction "RESET_19") (pintype "bidirectional"))
    )
    (net (code "84") (name "unconnected-(IC4-USB_DN-Pad11)") (class "Default")
      (node (ref "IC4") (pin "11") (pinfunction "USB_DN_11") (pintype "bidirectional"))
    )
    (net (code "85") (name "unconnected-(IC4-USB_DP-Pad12)") (class "Default")
      (node (ref "IC4") (pin "12") (pinfunction "USB_DP_12") (pintype "bidirectional"))
    )
    (net (code "86") (name "unconnected-(IC4-VDD_CHG-Pad38)") (class "Default")
      (node (ref "IC4") (pin "38") (pinfunction "VDD_CHG_38") (pintype "bidirectional"))
    )
    (net (code "87") (name "unconnected-(J2-SWITCH-Pad5)") (class "Default")
      (node (ref "J2") (pin "5") (pinfunction "SWITCH_5") (pintype "bidirectional"))
    )
  )
)
